# ThrusterBoardV1_1.net
KiCad netlist of a schematic drawn in EAGLE
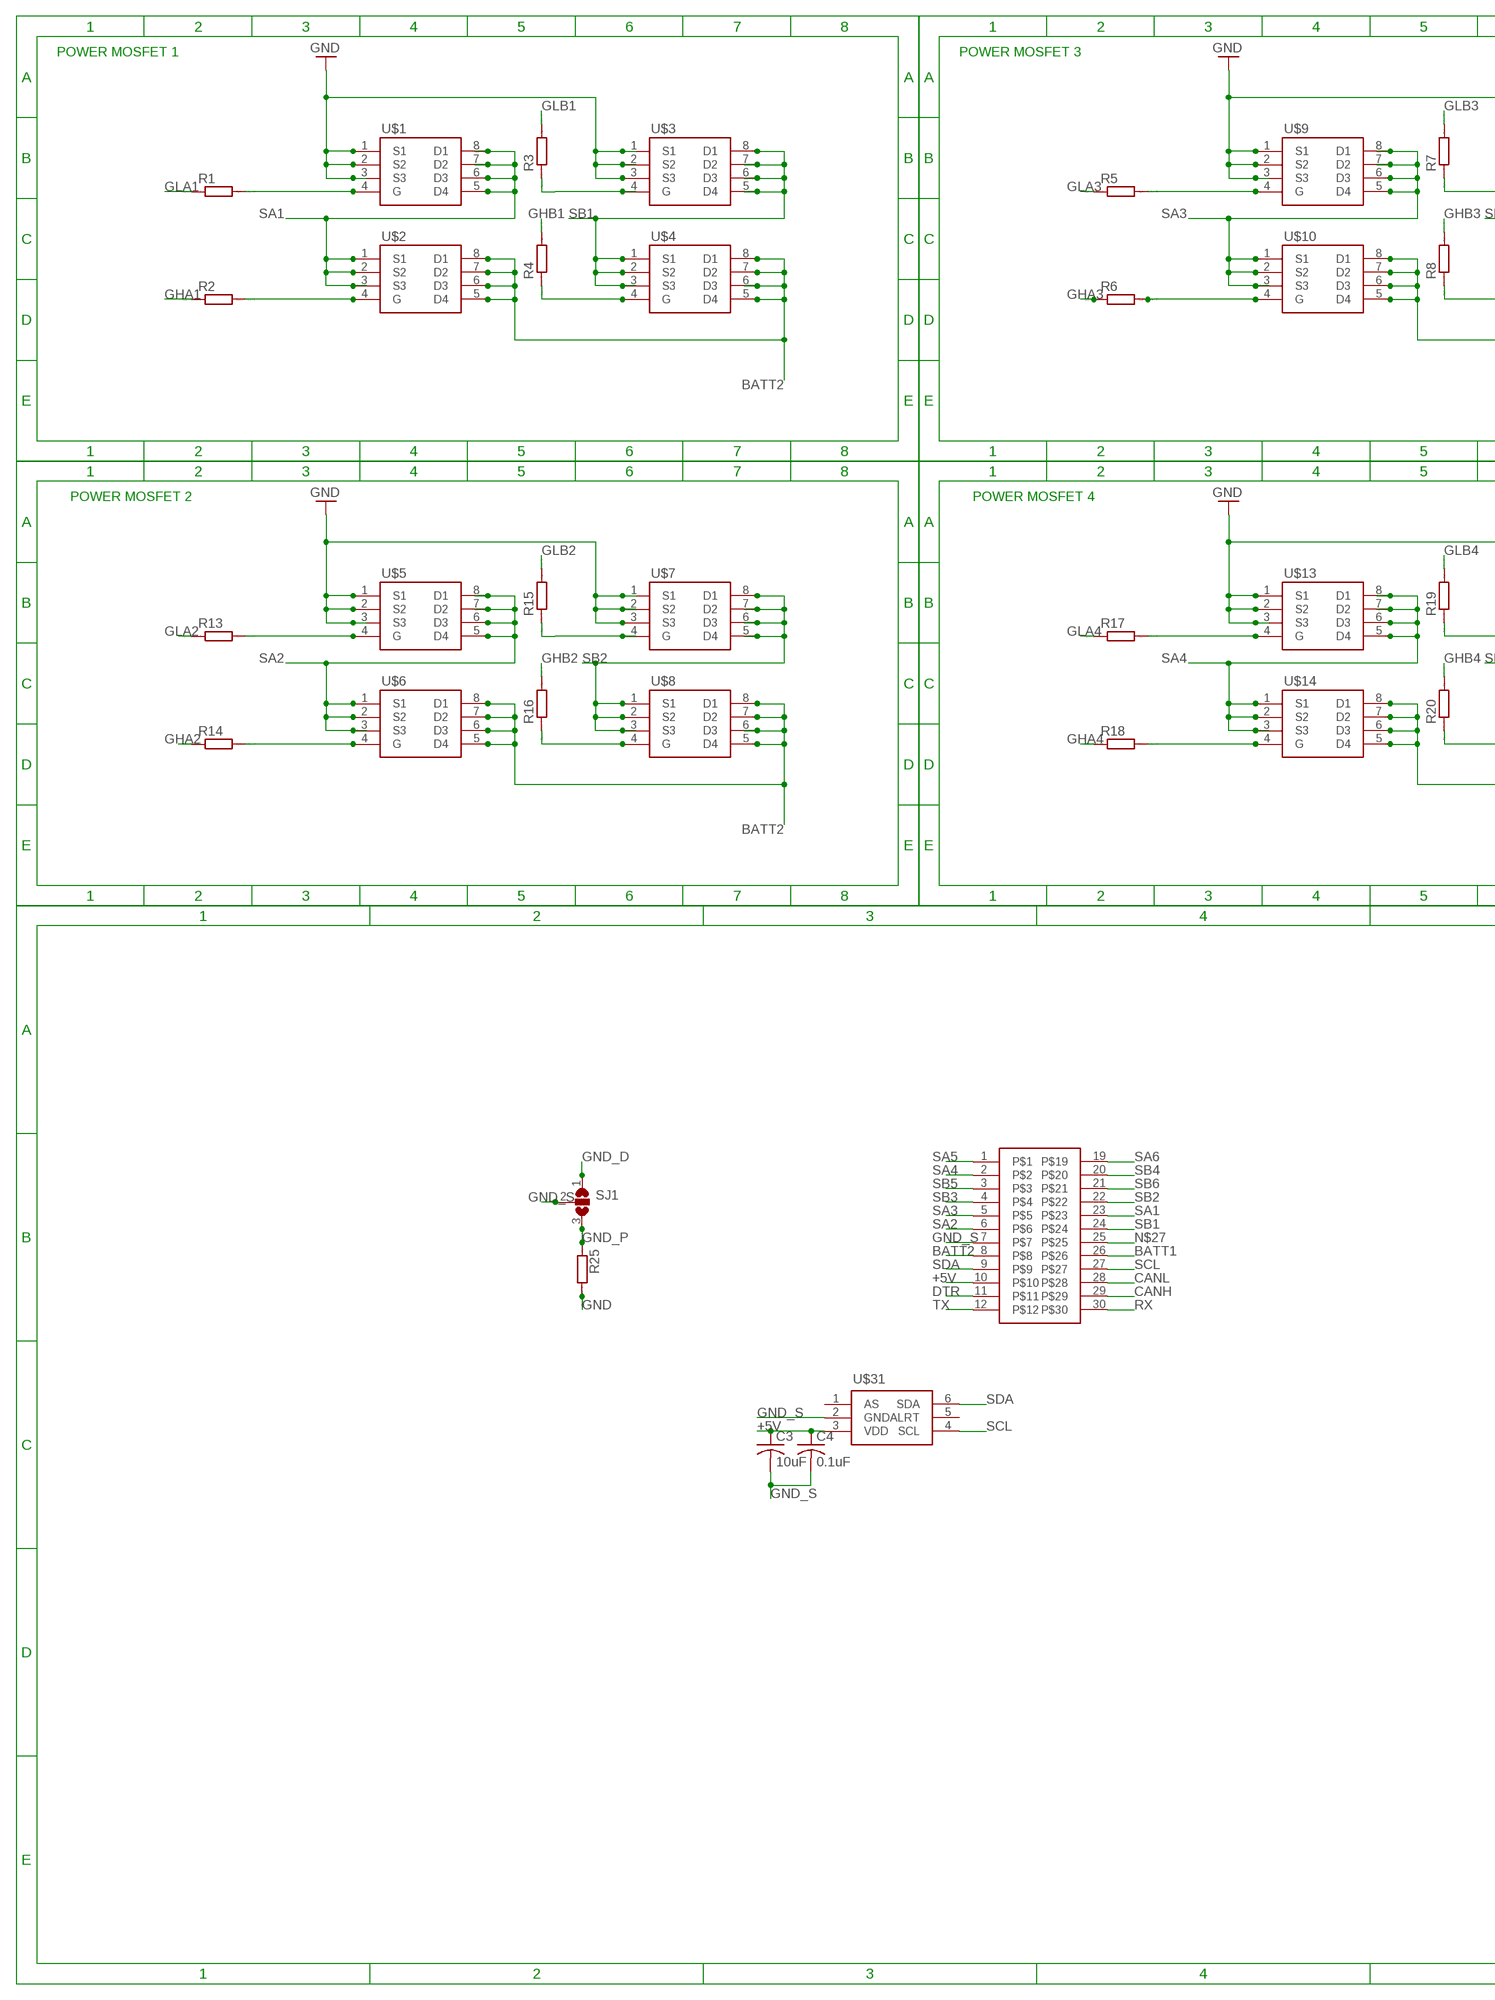
[diagram p0: schematic, sheet 1, part 1 of 2]
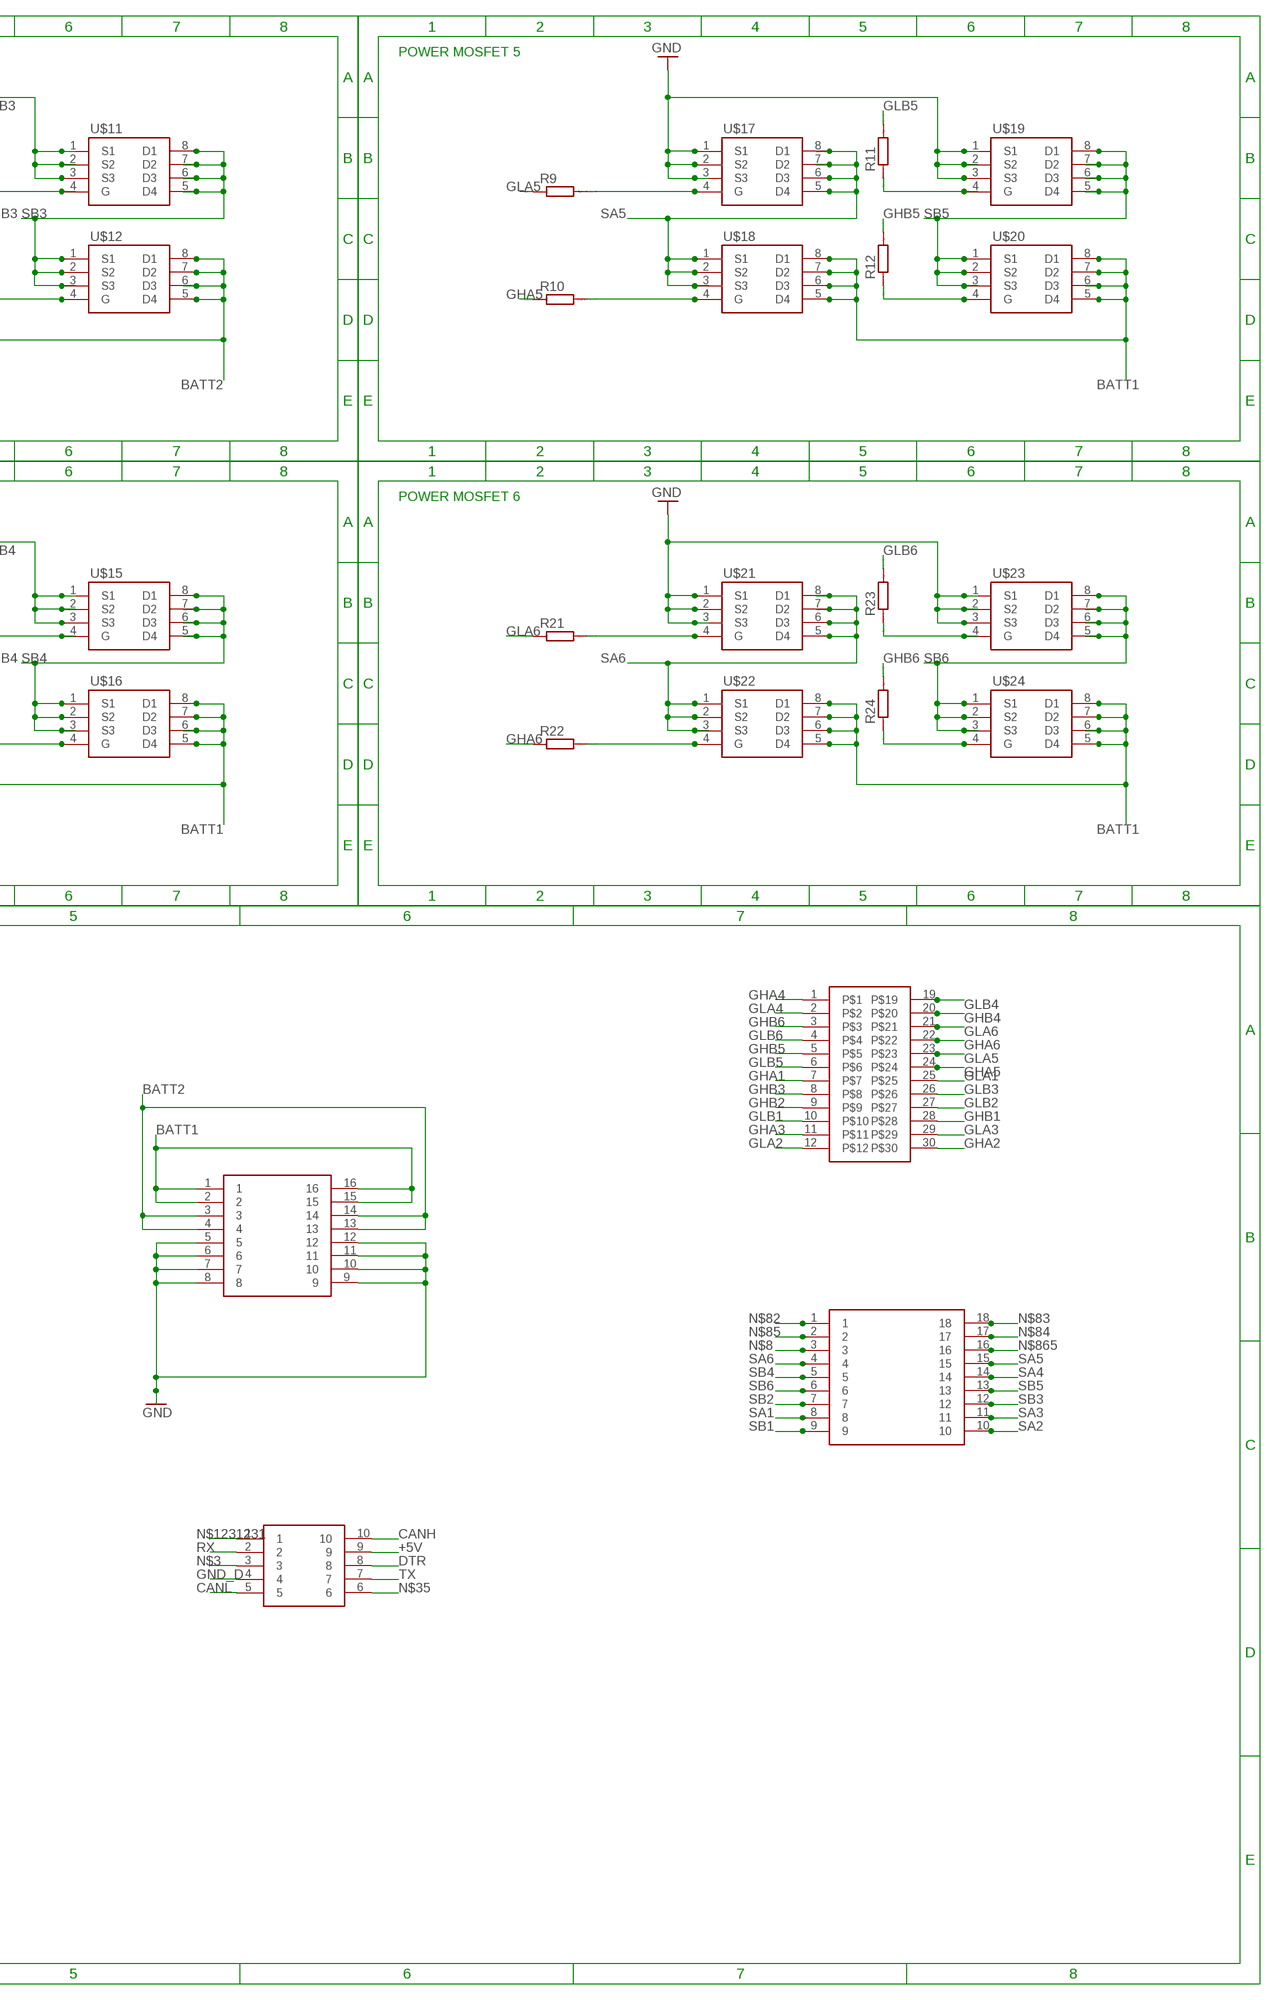
[diagram p1: schematic, sheet 1, part 2 of 2]

(export (version "E")
  (design (tool "Eeschema 10.0.6"))
  (components
    (comp (ref "C3")
      (value "10uF")
      (footprint "eagle-import:C0805")
      (libsource (lib "eagle-import") (part "C-USC0805"))
    )
    (comp (ref "C4")
      (value "0.1uF")
      (footprint "eagle-import:C0805")
      (libsource (lib "eagle-import") (part "C-USC0805"))
    )
    (comp (ref "R1") (value "R") (footprint "eagle-import:R0805") (libsource (lib "eagle-import") (part "R")))
    (comp (ref "R2") (value "R") (footprint "eagle-import:R0805") (libsource (lib "eagle-import") (part "R")))
    (comp (ref "R3") (value "R") (footprint "eagle-import:R0805") (libsource (lib "eagle-import") (part "R")))
    (comp (ref "R4") (value "R") (footprint "eagle-import:R0805") (libsource (lib "eagle-import") (part "R")))
    (comp (ref "R5") (value "R") (footprint "eagle-import:R0805") (libsource (lib "eagle-import") (part "R")))
    (comp (ref "R6") (value "R") (footprint "eagle-import:R0805") (libsource (lib "eagle-import") (part "R")))
    (comp (ref "R7") (value "R") (footprint "eagle-import:R0805") (libsource (lib "eagle-import") (part "R")))
    (comp (ref "R8") (value "R") (footprint "eagle-import:R0805") (libsource (lib "eagle-import") (part "R")))
    (comp (ref "R9") (value "R") (footprint "eagle-import:R0805") (libsource (lib "eagle-import") (part "R")))
    (comp (ref "R10")
      (value "R")
      (footprint "eagle-import:R0805")
      (libsource (lib "eagle-import") (part "R"))
    )
    (comp (ref "R11")
      (value "R")
      (footprint "eagle-import:R0805")
      (libsource (lib "eagle-import") (part "R"))
    )
    (comp (ref "R12")
      (value "R")
      (footprint "eagle-import:R0805")
      (libsource (lib "eagle-import") (part "R"))
    )
    (comp (ref "R13")
      (value "R")
      (footprint "eagle-import:R0805")
      (libsource (lib "eagle-import") (part "R"))
    )
    (comp (ref "R14")
      (value "R")
      (footprint "eagle-import:R0805")
      (libsource (lib "eagle-import") (part "R"))
    )
    (comp (ref "R15")
      (value "R")
      (footprint "eagle-import:R0805")
      (libsource (lib "eagle-import") (part "R"))
    )
    (comp (ref "R16")
      (value "R")
      (footprint "eagle-import:R0805")
      (libsource (lib "eagle-import") (part "R"))
    )
    (comp (ref "R17")
      (value "R")
      (footprint "eagle-import:R0805")
      (libsource (lib "eagle-import") (part "R"))
    )
    (comp (ref "R18")
      (value "R")
      (footprint "eagle-import:R0805")
      (libsource (lib "eagle-import") (part "R"))
    )
    (comp (ref "R19")
      (value "R")
      (footprint "eagle-import:R0805")
      (libsource (lib "eagle-import") (part "R"))
    )
    (comp (ref "R20")
      (value "R")
      (footprint "eagle-import:R0805")
      (libsource (lib "eagle-import") (part "R"))
    )
    (comp (ref "R21")
      (value "R")
      (footprint "eagle-import:R0805")
      (libsource (lib "eagle-import") (part "R"))
    )
    (comp (ref "R22")
      (value "R")
      (footprint "eagle-import:R0805")
      (libsource (lib "eagle-import") (part "R"))
    )
    (comp (ref "R23")
      (value "R")
      (footprint "eagle-import:R0805")
      (libsource (lib "eagle-import") (part "R"))
    )
    (comp (ref "R24")
      (value "R")
      (footprint "eagle-import:R0805")
      (libsource (lib "eagle-import") (part "R"))
    )
    (comp (ref "R25")
      (value "R")
      (footprint "eagle-import:R0805")
      (libsource (lib "eagle-import") (part "R"))
    )
    (comp (ref "SJ1")
      (value "SJ2W")
      (footprint "eagle-import:SJ_2")
      (libsource (lib "eagle-import") (part "SJ2W"))
    )
    (comp (ref "U$1")
      (value "IRF7842PBF")
      (footprint "eagle-import:SO-8")
      (libsource (lib "eagle-import") (part "IRF7842PBF"))
    )
    (comp (ref "U$2")
      (value "IRF7842PBF")
      (footprint "eagle-import:SO-8")
      (libsource (lib "eagle-import") (part "IRF7842PBF"))
    )
    (comp (ref "U$3")
      (value "IRF7842PBF")
      (footprint "eagle-import:SO-8")
      (libsource (lib "eagle-import") (part "IRF7842PBF"))
    )
    (comp (ref "U$4")
      (value "IRF7842PBF")
      (footprint "eagle-import:SO-8")
      (libsource (lib "eagle-import") (part "IRF7842PBF"))
    )
    (comp (ref "U$5")
      (value "IRF7842PBF")
      (footprint "eagle-import:SO-8")
      (libsource (lib "eagle-import") (part "IRF7842PBF"))
    )
    (comp (ref "U$6")
      (value "IRF7842PBF")
      (footprint "eagle-import:SO-8")
      (libsource (lib "eagle-import") (part "IRF7842PBF"))
    )
    (comp (ref "U$7")
      (value "IRF7842PBF")
      (footprint "eagle-import:SO-8")
      (libsource (lib "eagle-import") (part "IRF7842PBF"))
    )
    (comp (ref "U$8")
      (value "IRF7842PBF")
      (footprint "eagle-import:SO-8")
      (libsource (lib "eagle-import") (part "IRF7842PBF"))
    )
    (comp (ref "U$9")
      (value "IRF7842PBF")
      (footprint "eagle-import:SO-8")
      (libsource (lib "eagle-import") (part "IRF7842PBF"))
    )
    (comp (ref "U$10")
      (value "IRF7842PBF")
      (footprint "eagle-import:SO-8")
      (libsource (lib "eagle-import") (part "IRF7842PBF"))
    )
    (comp (ref "U$11")
      (value "IRF7842PBF")
      (footprint "eagle-import:SO-8")
      (libsource (lib "eagle-import") (part "IRF7842PBF"))
    )
    (comp (ref "U$12")
      (value "IRF7842PBF")
      (footprint "eagle-import:SO-8")
      (libsource (lib "eagle-import") (part "IRF7842PBF"))
    )
    (comp (ref "U$13")
      (value "IRF7842PBF")
      (footprint "eagle-import:SO-8")
      (libsource (lib "eagle-import") (part "IRF7842PBF"))
    )
    (comp (ref "U$14")
      (value "IRF7842PBF")
      (footprint "eagle-import:SO-8")
      (libsource (lib "eagle-import") (part "IRF7842PBF"))
    )
    (comp (ref "U$15")
      (value "IRF7842PBF")
      (footprint "eagle-import:SO-8")
      (libsource (lib "eagle-import") (part "IRF7842PBF"))
    )
    (comp (ref "U$16")
      (value "IRF7842PBF")
      (footprint "eagle-import:SO-8")
      (libsource (lib "eagle-import") (part "IRF7842PBF"))
    )
    (comp (ref "U$17")
      (value "IRF7842PBF")
      (footprint "eagle-import:SO-8")
      (libsource (lib "eagle-import") (part "IRF7842PBF"))
    )
    (comp (ref "U$18")
      (value "IRF7842PBF")
      (footprint "eagle-import:SO-8")
      (libsource (lib "eagle-import") (part "IRF7842PBF"))
    )
    (comp (ref "U$19")
      (value "IRF7842PBF")
      (footprint "eagle-import:SO-8")
      (libsource (lib "eagle-import") (part "IRF7842PBF"))
    )
    (comp (ref "U$20")
      (value "IRF7842PBF")
      (footprint "eagle-import:SO-8")
      (libsource (lib "eagle-import") (part "IRF7842PBF"))
    )
    (comp (ref "U$21")
      (value "IRF7842PBF")
      (footprint "eagle-import:SO-8")
      (libsource (lib "eagle-import") (part "IRF7842PBF"))
    )
    (comp (ref "U$22")
      (value "IRF7842PBF")
      (footprint "eagle-import:SO-8")
      (libsource (lib "eagle-import") (part "IRF7842PBF"))
    )
    (comp (ref "U$23")
      (value "IRF7842PBF")
      (footprint "eagle-import:SO-8")
      (libsource (lib "eagle-import") (part "IRF7842PBF"))
    )
    (comp (ref "U$24")
      (value "IRF7842PBF")
      (footprint "eagle-import:SO-8")
      (libsource (lib "eagle-import") (part "IRF7842PBF"))
    )
    (comp (ref "U$25")
      (value "15-24-6163")
      (footprint "eagle-import:15-24-6163")
      (libsource (lib "eagle-import") (part "15-24-6163"))
    )
    (comp (ref "U$26")
      (value "50-36-1836")
      (footprint "eagle-import:50-36-1836")
      (libsource (lib "eagle-import") (part "50-36-1836"))
    )
    (comp (ref "U$27")
      (value "15-24-6103")
      (footprint "eagle-import:15-24-6103")
      (libsource (lib "eagle-import") (part "15-24-6103"))
    )
    (comp (ref "U$28")
      (value "15-45-3136")
      (footprint "eagle-import:15-45-3136")
      (libsource (lib "eagle-import") (part "15-45-3136"))
    )
    (comp (ref "U$29")
      (value "15-45-3136")
      (footprint "eagle-import:15-45-3136")
      (libsource (lib "eagle-import") (part "15-45-3136"))
    )
    (comp (ref "U$31")
      (value "AD7414")
      (footprint "eagle-import:SOT23-6")
      (libsource (lib "eagle-import") (part "AD7414"))
    )
  )
  (nets
    (net (code "1") (name "/+5V") (class "Default")
      (node (ref "C3") (pin "1") (pinfunction "1_1") (pintype "passive"))
      (node (ref "C4") (pin "1") (pinfunction "1_1") (pintype "passive"))
      (node (ref "U$27") (pin "9") (pinfunction "9_9") (pintype "bidirectional"))
      (node (ref "U$29") (pin "10") (pinfunction "P$10_10") (pintype "bidirectional"))
      (node (ref "U$31") (pin "3") (pinfunction "VDD_3") (pintype "bidirectional"))
    )
    (net (code "2") (name "/BATT1") (class "Default")
      (node (ref "U$14") (pin "5") (pinfunction "D4_5") (pintype "bidirectional"))
      (node (ref "U$14") (pin "6") (pinfunction "D3_6") (pintype "bidirectional"))
      (node (ref "U$14") (pin "7") (pinfunction "D2_7") (pintype "bidirectional"))
      (node (ref "U$14") (pin "8") (pinfunction "D1_8") (pintype "bidirectional"))
      (node (ref "U$16") (pin "5") (pinfunction "D4_5") (pintype "bidirectional"))
      (node (ref "U$16") (pin "6") (pinfunction "D3_6") (pintype "bidirectional"))
      (node (ref "U$16") (pin "7") (pinfunction "D2_7") (pintype "bidirectional"))
      (node (ref "U$16") (pin "8") (pinfunction "D1_8") (pintype "bidirectional"))
      (node (ref "U$18") (pin "5") (pinfunction "D4_5") (pintype "bidirectional"))
      (node (ref "U$18") (pin "6") (pinfunction "D3_6") (pintype "bidirectional"))
      (node (ref "U$18") (pin "7") (pinfunction "D2_7") (pintype "bidirectional"))
      (node (ref "U$18") (pin "8") (pinfunction "D1_8") (pintype "bidirectional"))
      (node (ref "U$20") (pin "5") (pinfunction "D4_5") (pintype "bidirectional"))
      (node (ref "U$20") (pin "6") (pinfunction "D3_6") (pintype "bidirectional"))
      (node (ref "U$20") (pin "7") (pinfunction "D2_7") (pintype "bidirectional"))
      (node (ref "U$20") (pin "8") (pinfunction "D1_8") (pintype "bidirectional"))
      (node (ref "U$22") (pin "5") (pinfunction "D4_5") (pintype "bidirectional"))
      (node (ref "U$22") (pin "6") (pinfunction "D3_6") (pintype "bidirectional"))
      (node (ref "U$22") (pin "7") (pinfunction "D2_7") (pintype "bidirectional"))
      (node (ref "U$22") (pin "8") (pinfunction "D1_8") (pintype "bidirectional"))
      (node (ref "U$24") (pin "5") (pinfunction "D4_5") (pintype "bidirectional"))
      (node (ref "U$24") (pin "6") (pinfunction "D3_6") (pintype "bidirectional"))
      (node (ref "U$24") (pin "7") (pinfunction "D2_7") (pintype "bidirectional"))
      (node (ref "U$24") (pin "8") (pinfunction "D1_8") (pintype "bidirectional"))
      (node (ref "U$25") (pin "1") (pinfunction "1_1") (pintype "bidirectional"))
      (node (ref "U$25") (pin "15") (pinfunction "15_15") (pintype "bidirectional"))
      (node (ref "U$25") (pin "16") (pinfunction "16_16") (pintype "bidirectional"))
      (node (ref "U$25") (pin "2") (pinfunction "2_2") (pintype "bidirectional"))
      (node (ref "U$29") (pin "26") (pinfunction "P$26_26") (pintype "bidirectional"))
    )
    (net (code "3") (name "/BATT2") (class "Default")
      (node (ref "U$10") (pin "5") (pinfunction "D4_5") (pintype "bidirectional"))
      (node (ref "U$10") (pin "6") (pinfunction "D3_6") (pintype "bidirectional"))
      (node (ref "U$10") (pin "7") (pinfunction "D2_7") (pintype "bidirectional"))
      (node (ref "U$10") (pin "8") (pinfunction "D1_8") (pintype "bidirectional"))
      (node (ref "U$12") (pin "5") (pinfunction "D4_5") (pintype "bidirectional"))
      (node (ref "U$12") (pin "6") (pinfunction "D3_6") (pintype "bidirectional"))
      (node (ref "U$12") (pin "7") (pinfunction "D2_7") (pintype "bidirectional"))
      (node (ref "U$12") (pin "8") (pinfunction "D1_8") (pintype "bidirectional"))
      (node (ref "U$2") (pin "5") (pinfunction "D4_5") (pintype "bidirectional"))
      (node (ref "U$2") (pin "6") (pinfunction "D3_6") (pintype "bidirectional"))
      (node (ref "U$2") (pin "7") (pinfunction "D2_7") (pintype "bidirectional"))
      (node (ref "U$2") (pin "8") (pinfunction "D1_8") (pintype "bidirectional"))
      (node (ref "U$25") (pin "13") (pinfunction "13_13") (pintype "bidirectional"))
      (node (ref "U$25") (pin "14") (pinfunction "14_14") (pintype "bidirectional"))
      (node (ref "U$25") (pin "3") (pinfunction "3_3") (pintype "bidirectional"))
      (node (ref "U$25") (pin "4") (pinfunction "4_4") (pintype "bidirectional"))
      (node (ref "U$29") (pin "8") (pinfunction "P$8_8") (pintype "bidirectional"))
      (node (ref "U$4") (pin "5") (pinfunction "D4_5") (pintype "bidirectional"))
      (node (ref "U$4") (pin "6") (pinfunction "D3_6") (pintype "bidirectional"))
      (node (ref "U$4") (pin "7") (pinfunction "D2_7") (pintype "bidirectional"))
      (node (ref "U$4") (pin "8") (pinfunction "D1_8") (pintype "bidirectional"))
      (node (ref "U$6") (pin "5") (pinfunction "D4_5") (pintype "bidirectional"))
      (node (ref "U$6") (pin "6") (pinfunction "D3_6") (pintype "bidirectional"))
      (node (ref "U$6") (pin "7") (pinfunction "D2_7") (pintype "bidirectional"))
      (node (ref "U$6") (pin "8") (pinfunction "D1_8") (pintype "bidirectional"))
      (node (ref "U$8") (pin "5") (pinfunction "D4_5") (pintype "bidirectional"))
      (node (ref "U$8") (pin "6") (pinfunction "D3_6") (pintype "bidirectional"))
      (node (ref "U$8") (pin "7") (pinfunction "D2_7") (pintype "bidirectional"))
      (node (ref "U$8") (pin "8") (pinfunction "D1_8") (pintype "bidirectional"))
    )
    (net (code "4") (name "/CANH") (class "Default")
      (node (ref "U$27") (pin "10") (pinfunction "10_10") (pintype "bidirectional"))
      (node (ref "U$29") (pin "29") (pinfunction "P$29_29") (pintype "bidirectional"))
    )
    (net (code "5") (name "/CANL") (class "Default")
      (node (ref "U$27") (pin "5") (pinfunction "5_5") (pintype "bidirectional"))
      (node (ref "U$29") (pin "28") (pinfunction "P$28_28") (pintype "bidirectional"))
    )
    (net (code "6") (name "/DTR") (class "Default")
      (node (ref "U$27") (pin "8") (pinfunction "8_8") (pintype "bidirectional"))
      (node (ref "U$29") (pin "11") (pinfunction "P$11_11") (pintype "bidirectional"))
    )
    (net (code "7") (name "/GHA1") (class "Default")
      (node (ref "R2") (pin "1") (pinfunction "1_1") (pintype "passive"))
      (node (ref "U$28") (pin "7") (pinfunction "P$7_7") (pintype "bidirectional"))
    )
    (net (code "8") (name "/GHA2") (class "Default")
      (node (ref "R14") (pin "1") (pinfunction "1_1") (pintype "passive"))
      (node (ref "U$28") (pin "30") (pinfunction "P$30_30") (pintype "bidirectional"))
    )
    (net (code "9") (name "/GHA3") (class "Default")
      (node (ref "R6") (pin "1") (pinfunction "1_1") (pintype "passive"))
      (node (ref "U$28") (pin "11") (pinfunction "P$11_11") (pintype "bidirectional"))
    )
    (net (code "10") (name "/GHA4") (class "Default")
      (node (ref "R18") (pin "1") (pinfunction "1_1") (pintype "passive"))
      (node (ref "U$28") (pin "1") (pinfunction "P$1_1") (pintype "bidirectional"))
    )
    (net (code "11") (name "/GHA5") (class "Default")
      (node (ref "R10") (pin "1") (pinfunction "1_1") (pintype "passive"))
      (node (ref "U$28") (pin "24") (pinfunction "P$24_24") (pintype "bidirectional"))
    )
    (net (code "12") (name "/GHA6") (class "Default")
      (node (ref "R22") (pin "1") (pinfunction "1_1") (pintype "passive"))
      (node (ref "U$28") (pin "22") (pinfunction "P$22_22") (pintype "bidirectional"))
    )
    (net (code "13") (name "/GHB1") (class "Default")
      (node (ref "R4") (pin "2") (pinfunction "2_2") (pintype "passive"))
      (node (ref "U$28") (pin "28") (pinfunction "P$28_28") (pintype "bidirectional"))
    )
    (net (code "14") (name "/GHB2") (class "Default")
      (node (ref "R16") (pin "2") (pinfunction "2_2") (pintype "passive"))
      (node (ref "U$28") (pin "9") (pinfunction "P$9_9") (pintype "bidirectional"))
    )
    (net (code "15") (name "/GHB3") (class "Default")
      (node (ref "R8") (pin "2") (pinfunction "2_2") (pintype "passive"))
      (node (ref "U$28") (pin "8") (pinfunction "P$8_8") (pintype "bidirectional"))
    )
    (net (code "16") (name "/GHB4") (class "Default")
      (node (ref "R20") (pin "2") (pinfunction "2_2") (pintype "passive"))
      (node (ref "U$28") (pin "20") (pinfunction "P$20_20") (pintype "bidirectional"))
    )
    (net (code "17") (name "/GHB5") (class "Default")
      (node (ref "R12") (pin "2") (pinfunction "2_2") (pintype "passive"))
      (node (ref "U$28") (pin "5") (pinfunction "P$5_5") (pintype "bidirectional"))
    )
    (net (code "18") (name "/GHB6") (class "Default")
      (node (ref "R24") (pin "2") (pinfunction "2_2") (pintype "passive"))
      (node (ref "U$28") (pin "3") (pinfunction "P$3_3") (pintype "bidirectional"))
    )
    (net (code "19") (name "/GLA1") (class "Default")
      (node (ref "R1") (pin "1") (pinfunction "1_1") (pintype "passive"))
      (node (ref "U$28") (pin "25") (pinfunction "P$25_25") (pintype "bidirectional"))
    )
    (net (code "20") (name "/GLA2") (class "Default")
      (node (ref "R13") (pin "1") (pinfunction "1_1") (pintype "passive"))
      (node (ref "U$28") (pin "12") (pinfunction "P$12_12") (pintype "bidirectional"))
    )
    (net (code "21") (name "/GLA3") (class "Default")
      (node (ref "R5") (pin "1") (pinfunction "1_1") (pintype "passive"))
      (node (ref "U$28") (pin "29") (pinfunction "P$29_29") (pintype "bidirectional"))
    )
    (net (code "22") (name "/GLA4") (class "Default")
      (node (ref "R17") (pin "1") (pinfunction "1_1") (pintype "passive"))
      (node (ref "U$28") (pin "2") (pinfunction "P$2_2") (pintype "bidirectional"))
    )
    (net (code "23") (name "/GLA5") (class "Default")
      (node (ref "R9") (pin "1") (pinfunction "1_1") (pintype "passive"))
      (node (ref "U$28") (pin "23") (pinfunction "P$23_23") (pintype "bidirectional"))
    )
    (net (code "24") (name "/GLA6") (class "Default")
      (node (ref "R21") (pin "1") (pinfunction "1_1") (pintype "passive"))
      (node (ref "U$28") (pin "21") (pinfunction "P$21_21") (pintype "bidirectional"))
    )
    (net (code "25") (name "/GLB1") (class "Default")
      (node (ref "R3") (pin "2") (pinfunction "2_2") (pintype "passive"))
      (node (ref "U$28") (pin "10") (pinfunction "P$10_10") (pintype "bidirectional"))
    )
    (net (code "26") (name "/GLB2") (class "Default")
      (node (ref "R15") (pin "2") (pinfunction "2_2") (pintype "passive"))
      (node (ref "U$28") (pin "27") (pinfunction "P$27_27") (pintype "bidirectional"))
    )
    (net (code "27") (name "/GLB3") (class "Default")
      (node (ref "R7") (pin "2") (pinfunction "2_2") (pintype "passive"))
      (node (ref "U$28") (pin "26") (pinfunction "P$26_26") (pintype "bidirectional"))
    )
    (net (code "28") (name "/GLB4") (class "Default")
      (node (ref "R19") (pin "2") (pinfunction "2_2") (pintype "passive"))
      (node (ref "U$28") (pin "19") (pinfunction "P$19_19") (pintype "bidirectional"))
    )
    (net (code "29") (name "/GLB5") (class "Default")
      (node (ref "R11") (pin "2") (pinfunction "2_2") (pintype "passive"))
      (node (ref "U$28") (pin "6") (pinfunction "P$6_6") (pintype "bidirectional"))
    )
    (net (code "30") (name "/GLB6") (class "Default")
      (node (ref "R23") (pin "2") (pinfunction "2_2") (pintype "passive"))
      (node (ref "U$28") (pin "4") (pinfunction "P$4_4") (pintype "bidirectional"))
    )
    (net (code "31") (name "/GND_D") (class "Default")
      (node (ref "SJ1") (pin "1") (pinfunction "1_1") (pintype "passive"))
      (node (ref "U$27") (pin "4") (pinfunction "4_4") (pintype "bidirectional"))
    )
    (net (code "32") (name "/GND_P") (class "Default")
      (node (ref "R25") (pin "1") (pinfunction "1_1") (pintype "passive"))
      (node (ref "SJ1") (pin "3") (pinfunction "3_3") (pintype "passive"))
    )
    (net (code "33") (name "/GND_S") (class "Default")
      (node (ref "C3") (pin "2") (pinfunction "2_2") (pintype "passive"))
      (node (ref "C4") (pin "2") (pinfunction "2_2") (pintype "passive"))
      (node (ref "SJ1") (pin "2") (pinfunction "2_2") (pintype "passive"))
      (node (ref "U$29") (pin "7") (pinfunction "P$7_7") (pintype "bidirectional"))
      (node (ref "U$31") (pin "2") (pinfunction "GND_2") (pintype "bidirectional"))
    )
    (net (code "34") (name "/N$3") (class "Default")
      (node (ref "U$27") (pin "3") (pinfunction "3_3") (pintype "bidirectional"))
    )
    (net (code "35") (name "/N$8") (class "Default")
      (node (ref "U$26") (pin "3") (pinfunction "3_3") (pintype "bidirectional"))
    )
    (net (code "36") (name "/N$27") (class "Default")
      (node (ref "U$29") (pin "25") (pinfunction "P$25_25") (pintype "bidirectional"))
    )
    (net (code "37") (name "/N$35") (class "Default")
      (node (ref "U$27") (pin "6") (pinfunction "6_6") (pintype "bidirectional"))
    )
    (net (code "38") (name "/N$82") (class "Default")
      (node (ref "U$26") (pin "1") (pinfunction "1_1") (pintype "bidirectional"))
    )
    (net (code "39") (name "/N$83") (class "Default")
      (node (ref "U$26") (pin "18") (pinfunction "18_18") (pintype "bidirectional"))
    )
    (net (code "40") (name "/N$84") (class "Default")
      (node (ref "U$26") (pin "17") (pinfunction "17_17") (pintype "bidirectional"))
    )
    (net (code "41") (name "/N$85") (class "Default")
      (node (ref "U$26") (pin "2") (pinfunction "2_2") (pintype "bidirectional"))
    )
    (net (code "42") (name "/N$865") (class "Default")
      (node (ref "U$26") (pin "16") (pinfunction "16_16") (pintype "bidirectional"))
    )
    (net (code "43") (name "/N$1231231") (class "Default")
      (node (ref "U$27") (pin "1") (pinfunction "1_1") (pintype "bidirectional"))
    )
    (net (code "44") (name "/RX") (class "Default")
      (node (ref "U$27") (pin "2") (pinfunction "2_2") (pintype "bidirectional"))
      (node (ref "U$29") (pin "30") (pinfunction "P$30_30") (pintype "bidirectional"))
    )
    (net (code "45") (name "/SA1") (class "Default")
      (node (ref "U$1") (pin "5") (pinfunction "D4_5") (pintype "bidirectional"))
      (node (ref "U$1") (pin "6") (pinfunction "D3_6") (pintype "bidirectional"))
      (node (ref "U$1") (pin "7") (pinfunction "D2_7") (pintype "bidirectional"))
      (node (ref "U$1") (pin "8") (pinfunction "D1_8") (pintype "bidirectional"))
      (node (ref "U$2") (pin "1") (pinfunction "S1_1") (pintype "bidirectional"))
      (node (ref "U$2") (pin "2") (pinfunction "S2_2") (pintype "bidirectional"))
      (node (ref "U$2") (pin "3") (pinfunction "S3_3") (pintype "bidirectional"))
      (node (ref "U$26") (pin "8") (pinfunction "8_8") (pintype "bidirectional"))
      (node (ref "U$29") (pin "23") (pinfunction "P$23_23") (pintype "bidirectional"))
    )
    (net (code "46") (name "/SA2") (class "Default")
      (node (ref "U$26") (pin "10") (pinfunction "10_10") (pintype "bidirectional"))
      (node (ref "U$29") (pin "6") (pinfunction "P$6_6") (pintype "bidirectional"))
      (node (ref "U$5") (pin "5") (pinfunction "D4_5") (pintype "bidirectional"))
      (node (ref "U$5") (pin "6") (pinfunction "D3_6") (pintype "bidirectional"))
      (node (ref "U$5") (pin "7") (pinfunction "D2_7") (pintype "bidirectional"))
      (node (ref "U$5") (pin "8") (pinfunction "D1_8") (pintype "bidirectional"))
      (node (ref "U$6") (pin "1") (pinfunction "S1_1") (pintype "bidirectional"))
      (node (ref "U$6") (pin "2") (pinfunction "S2_2") (pintype "bidirectional"))
      (node (ref "U$6") (pin "3") (pinfunction "S3_3") (pintype "bidirectional"))
    )
    (net (code "47") (name "/SA3") (class "Default")
      (node (ref "U$10") (pin "1") (pinfunction "S1_1") (pintype "bidirectional"))
      (node (ref "U$10") (pin "2") (pinfunction "S2_2") (pintype "bidirectional"))
      (node (ref "U$10") (pin "3") (pinfunction "S3_3") (pintype "bidirectional"))
      (node (ref "U$26") (pin "11") (pinfunction "11_11") (pintype "bidirectional"))
      (node (ref "U$29") (pin "5") (pinfunction "P$5_5") (pintype "bidirectional"))
      (node (ref "U$9") (pin "5") (pinfunction "D4_5") (pintype "bidirectional"))
      (node (ref "U$9") (pin "6") (pinfunction "D3_6") (pintype "bidirectional"))
      (node (ref "U$9") (pin "7") (pinfunction "D2_7") (pintype "bidirectional"))
      (node (ref "U$9") (pin "8") (pinfunction "D1_8") (pintype "bidirectional"))
    )
    (net (code "48") (name "/SA4") (class "Default")
      (node (ref "U$13") (pin "5") (pinfunction "D4_5") (pintype "bidirectional"))
      (node (ref "U$13") (pin "6") (pinfunction "D3_6") (pintype "bidirectional"))
      (node (ref "U$13") (pin "7") (pinfunction "D2_7") (pintype "bidirectional"))
      (node (ref "U$13") (pin "8") (pinfunction "D1_8") (pintype "bidirectional"))
      (node (ref "U$14") (pin "1") (pinfunction "S1_1") (pintype "bidirectional"))
      (node (ref "U$14") (pin "2") (pinfunction "S2_2") (pintype "bidirectional"))
      (node (ref "U$14") (pin "3") (pinfunction "S3_3") (pintype "bidirectional"))
      (node (ref "U$26") (pin "14") (pinfunction "14_14") (pintype "bidirectional"))
      (node (ref "U$29") (pin "2") (pinfunction "P$2_2") (pintype "bidirectional"))
    )
    (net (code "49") (name "/SA5") (class "Default")
      (node (ref "U$17") (pin "5") (pinfunction "D4_5") (pintype "bidirectional"))
      (node (ref "U$17") (pin "6") (pinfunction "D3_6") (pintype "bidirectional"))
      (node (ref "U$17") (pin "7") (pinfunction "D2_7") (pintype "bidirectional"))
      (node (ref "U$17") (pin "8") (pinfunction "D1_8") (pintype "bidirectional"))
      (node (ref "U$18") (pin "1") (pinfunction "S1_1") (pintype "bidirectional"))
      (node (ref "U$18") (pin "2") (pinfunction "S2_2") (pintype "bidirectional"))
      (node (ref "U$18") (pin "3") (pinfunction "S3_3") (pintype "bidirectional"))
      (node (ref "U$26") (pin "15") (pinfunction "15_15") (pintype "bidirectional"))
      (node (ref "U$29") (pin "1") (pinfunction "P$1_1") (pintype "bidirectional"))
    )
    (net (code "50") (name "/SA6") (class "Default")
      (node (ref "U$21") (pin "5") (pinfunction "D4_5") (pintype "bidirectional"))
      (node (ref "U$21") (pin "6") (pinfunction "D3_6") (pintype "bidirectional"))
      (node (ref "U$21") (pin "7") (pinfunction "D2_7") (pintype "bidirectional"))
      (node (ref "U$21") (pin "8") (pinfunction "D1_8") (pintype "bidirectional"))
      (node (ref "U$22") (pin "1") (pinfunction "S1_1") (pintype "bidirectional"))
      (node (ref "U$22") (pin "2") (pinfunction "S2_2") (pintype "bidirectional"))
      (node (ref "U$22") (pin "3") (pinfunction "S3_3") (pintype "bidirectional"))
      (node (ref "U$26") (pin "4") (pinfunction "4_4") (pintype "bidirectional"))
      (node (ref "U$29") (pin "19") (pinfunction "P$19_19") (pintype "bidirectional"))
    )
    (net (code "51") (name "/SB1") (class "Default")
      (node (ref "U$26") (pin "9") (pinfunction "9_9") (pintype "bidirectional"))
      (node (ref "U$29") (pin "24") (pinfunction "P$24_24") (pintype "bidirectional"))
      (node (ref "U$3") (pin "5") (pinfunction "D4_5") (pintype "bidirectional"))
      (node (ref "U$3") (pin "6") (pinfunction "D3_6") (pintype "bidirectional"))
      (node (ref "U$3") (pin "7") (pinfunction "D2_7") (pintype "bidirectional"))
      (node (ref "U$3") (pin "8") (pinfunction "D1_8") (pintype "bidirectional"))
      (node (ref "U$4") (pin "1") (pinfunction "S1_1") (pintype "bidirectional"))
      (node (ref "U$4") (pin "2") (pinfunction "S2_2") (pintype "bidirectional"))
      (node (ref "U$4") (pin "3") (pinfunction "S3_3") (pintype "bidirectional"))
    )
    (net (code "52") (name "/SB2") (class "Default")
      (node (ref "U$26") (pin "7") (pinfunction "7_7") (pintype "bidirectional"))
      (node (ref "U$29") (pin "22") (pinfunction "P$22_22") (pintype "bidirectional"))
      (node (ref "U$7") (pin "5") (pinfunction "D4_5") (pintype "bidirectional"))
      (node (ref "U$7") (pin "6") (pinfunction "D3_6") (pintype "bidirectional"))
      (node (ref "U$7") (pin "7") (pinfunction "D2_7") (pintype "bidirectional"))
      (node (ref "U$7") (pin "8") (pinfunction "D1_8") (pintype "bidirectional"))
      (node (ref "U$8") (pin "1") (pinfunction "S1_1") (pintype "bidirectional"))
      (node (ref "U$8") (pin "2") (pinfunction "S2_2") (pintype "bidirectional"))
      (node (ref "U$8") (pin "3") (pinfunction "S3_3") (pintype "bidirectional"))
    )
    (net (code "53") (name "/SB3") (class "Default")
      (node (ref "U$11") (pin "5") (pinfunction "D4_5") (pintype "bidirectional"))
      (node (ref "U$11") (pin "6") (pinfunction "D3_6") (pintype "bidirectional"))
      (node (ref "U$11") (pin "7") (pinfunction "D2_7") (pintype "bidirectional"))
      (node (ref "U$11") (pin "8") (pinfunction "D1_8") (pintype "bidirectional"))
      (node (ref "U$12") (pin "1") (pinfunction "S1_1") (pintype "bidirectional"))
      (node (ref "U$12") (pin "2") (pinfunction "S2_2") (pintype "bidirectional"))
      (node (ref "U$12") (pin "3") (pinfunction "S3_3") (pintype "bidirectional"))
      (node (ref "U$26") (pin "12") (pinfunction "12_12") (pintype "bidirectional"))
      (node (ref "U$29") (pin "4") (pinfunction "P$4_4") (pintype "bidirectional"))
    )
    (net (code "54") (name "/SB4") (class "Default")
      (node (ref "U$15") (pin "5") (pinfunction "D4_5") (pintype "bidirectional"))
      (node (ref "U$15") (pin "6") (pinfunction "D3_6") (pintype "bidirectional"))
      (node (ref "U$15") (pin "7") (pinfunction "D2_7") (pintype "bidirectional"))
      (node (ref "U$15") (pin "8") (pinfunction "D1_8") (pintype "bidirectional"))
      (node (ref "U$16") (pin "1") (pinfunction "S1_1") (pintype "bidirectional"))
      (node (ref "U$16") (pin "2") (pinfunction "S2_2") (pintype "bidirectional"))
      (node (ref "U$16") (pin "3") (pinfunction "S3_3") (pintype "bidirectional"))
      (node (ref "U$26") (pin "5") (pinfunction "5_5") (pintype "bidirectional"))
      (node (ref "U$29") (pin "20") (pinfunction "P$20_20") (pintype "bidirectional"))
    )
    (net (code "55") (name "/SB5") (class "Default")
      (node (ref "U$19") (pin "5") (pinfunction "D4_5") (pintype "bidirectional"))
      (node (ref "U$19") (pin "6") (pinfunction "D3_6") (pintype "bidirectional"))
      (node (ref "U$19") (pin "7") (pinfunction "D2_7") (pintype "bidirectional"))
      (node (ref "U$19") (pin "8") (pinfunction "D1_8") (pintype "bidirectional"))
      (node (ref "U$20") (pin "1") (pinfunction "S1_1") (pintype "bidirectional"))
      (node (ref "U$20") (pin "2") (pinfunction "S2_2") (pintype "bidirectional"))
      (node (ref "U$20") (pin "3") (pinfunction "S3_3") (pintype "bidirectional"))
      (node (ref "U$26") (pin "13") (pinfunction "13_13") (pintype "bidirectional"))
      (node (ref "U$29") (pin "3") (pinfunction "P$3_3") (pintype "bidirectional"))
    )
    (net (code "56") (name "/SB6") (class "Default")
      (node (ref "U$23") (pin "5") (pinfunction "D4_5") (pintype "bidirectional"))
      (node (ref "U$23") (pin "6") (pinfunction "D3_6") (pintype "bidirectional"))
      (node (ref "U$23") (pin "7") (pinfunction "D2_7") (pintype "bidirectional"))
      (node (ref "U$23") (pin "8") (pinfunction "D1_8") (pintype "bidirectional"))
      (node (ref "U$24") (pin "1") (pinfunction "S1_1") (pintype "bidirectional"))
      (node (ref "U$24") (pin "2") (pinfunction "S2_2") (pintype "bidirectional"))
      (node (ref "U$24") (pin "3") (pinfunction "S3_3") (pintype "bidirectional"))
      (node (ref "U$26") (pin "6") (pinfunction "6_6") (pintype "bidirectional"))
      (node (ref "U$29") (pin "21") (pinfunction "P$21_21") (pintype "bidirectional"))
    )
    (net (code "57") (name "/SCL") (class "Default")
      (node (ref "U$29") (pin "27") (pinfunction "P$27_27") (pintype "bidirectional"))
      (node (ref "U$31") (pin "4") (pinfunction "SCL_4") (pintype "bidirectional"))
    )
    (net (code "58") (name "/SDA") (class "Default")
      (node (ref "U$29") (pin "9") (pinfunction "P$9_9") (pintype "bidirectional"))
      (node (ref "U$31") (pin "6") (pinfunction "SDA_6") (pintype "bidirectional"))
    )
    (net (code "59") (name "/TX") (class "Default")
      (node (ref "U$27") (pin "7") (pinfunction "7_7") (pintype "bidirectional"))
      (node (ref "U$29") (pin "12") (pinfunction "P$12_12") (pintype "bidirectional"))
    )
    (net (code "60") (name "GND") (class "Default")
      (node (ref "R25") (pin "2") (pinfunction "2_2") (pintype "passive"))
      (node (ref "U$1") (pin "1") (pinfunction "S1_1") (pintype "bidirectional"))
      (node (ref "U$1") (pin "2") (pinfunction "S2_2") (pintype "bidirectional"))
      (node (ref "U$1") (pin "3") (pinfunction "S3_3") (pintype "bidirectional"))
      (node (ref "U$11") (pin "1") (pinfunction "S1_1") (pintype "bidirectional"))
      (node (ref "U$11") (pin "2") (pinfunction "S2_2") (pintype "bidirectional"))
      (node (ref "U$11") (pin "3") (pinfunction "S3_3") (pintype "bidirectional"))
      (node (ref "U$13") (pin "1") (pinfunction "S1_1") (pintype "bidirectional"))
      (node (ref "U$13") (pin "2") (pinfunction "S2_2") (pintype "bidirectional"))
      (node (ref "U$13") (pin "3") (pinfunction "S3_3") (pintype "bidirectional"))
      (node (ref "U$15") (pin "1") (pinfunction "S1_1") (pintype "bidirectional"))
      (node (ref "U$15") (pin "2") (pinfunction "S2_2") (pintype "bidirectional"))
      (node (ref "U$15") (pin "3") (pinfunction "S3_3") (pintype "bidirectional"))
      (node (ref "U$17") (pin "1") (pinfunction "S1_1") (pintype "bidirectional"))
      (node (ref "U$17") (pin "2") (pinfunction "S2_2") (pintype "bidirectional"))
      (node (ref "U$17") (pin "3") (pinfunction "S3_3") (pintype "bidirectional"))
      (node (ref "U$19") (pin "1") (pinfunction "S1_1") (pintype "bidirectional"))
      (node (ref "U$19") (pin "2") (pinfunction "S2_2") (pintype "bidirectional"))
      (node (ref "U$19") (pin "3") (pinfunction "S3_3") (pintype "bidirectional"))
      (node (ref "U$21") (pin "1") (pinfunction "S1_1") (pintype "bidirectional"))
      (node (ref "U$21") (pin "2") (pinfunction "S2_2") (pintype "bidirectional"))
      (node (ref "U$21") (pin "3") (pinfunction "S3_3") (pintype "bidirectional"))
      (node (ref "U$23") (pin "1") (pinfunction "S1_1") (pintype "bidirectional"))
      (node (ref "U$23") (pin "2") (pinfunction "S2_2") (pintype "bidirectional"))
      (node (ref "U$23") (pin "3") (pinfunction "S3_3") (pintype "bidirectional"))
      (node (ref "U$25") (pin "10") (pinfunction "10_10") (pintype "bidirectional"))
      (node (ref "U$25") (pin "11") (pinfunction "11_11") (pintype "bidirectional"))
      (node (ref "U$25") (pin "12") (pinfunction "12_12") (pintype "bidirectional"))
      (node (ref "U$25") (pin "5") (pinfunction "5_5") (pintype "bidirectional"))
      (node (ref "U$25") (pin "6") (pinfunction "6_6") (pintype "bidirectional"))
      (node (ref "U$25") (pin "7") (pinfunction "7_7") (pintype "bidirectional"))
      (node (ref "U$25") (pin "8") (pinfunction "8_8") (pintype "bidirectional"))
      (node (ref "U$25") (pin "9") (pinfunction "9_9") (pintype "bidirectional"))
      (node (ref "U$3") (pin "1") (pinfunction "S1_1") (pintype "bidirectional"))
      (node (ref "U$3") (pin "2") (pinfunction "S2_2") (pintype "bidirectional"))
      (node (ref "U$3") (pin "3") (pinfunction "S3_3") (pintype "bidirectional"))
      (node (ref "U$5") (pin "1") (pinfunction "S1_1") (pintype "bidirectional"))
      (node (ref "U$5") (pin "2") (pinfunction "S2_2") (pintype "bidirectional"))
      (node (ref "U$5") (pin "3") (pinfunction "S3_3") (pintype "bidirectional"))
      (node (ref "U$7") (pin "1") (pinfunction "S1_1") (pintype "bidirectional"))
      (node (ref "U$7") (pin "2") (pinfunction "S2_2") (pintype "bidirectional"))
      (node (ref "U$7") (pin "3") (pinfunction "S3_3") (pintype "bidirectional"))
      (node (ref "U$9") (pin "1") (pinfunction "S1_1") (pintype "bidirectional"))
      (node (ref "U$9") (pin "2") (pinfunction "S2_2") (pintype "bidirectional"))
      (node (ref "U$9") (pin "3") (pinfunction "S3_3") (pintype "bidirectional"))
    )
    (net (code "61") (name "Net-(U$1-G)") (class "Default")
      (node (ref "R1") (pin "2") (pinfunction "2_2") (pintype "passive"))
      (node (ref "U$1") (pin "4") (pinfunction "G_4") (pintype "bidirectional"))
    )
    (net (code "62") (name "Net-(U$2-G)") (class "Default")
      (node (ref "R2") (pin "2") (pinfunction "2_2") (pintype "passive"))
      (node (ref "U$2") (pin "4") (pinfunction "G_4") (pintype "bidirectional"))
    )
    (net (code "63") (name "Net-(U$3-G)") (class "Default")
      (node (ref "R3") (pin "1") (pinfunction "1_1") (pintype "passive"))
      (node (ref "U$3") (pin "4") (pinfunction "G_4") (pintype "bidirectional"))
    )
    (net (code "64") (name "Net-(U$4-G)") (class "Default")
      (node (ref "R4") (pin "1") (pinfunction "1_1") (pintype "passive"))
      (node (ref "U$4") (pin "4") (pinfunction "G_4") (pintype "bidirectional"))
    )
    (net (code "65") (name "Net-(U$5-G)") (class "Default")
      (node (ref "R13") (pin "2") (pinfunction "2_2") (pintype "passive"))
      (node (ref "U$5") (pin "4") (pinfunction "G_4") (pintype "bidirectional"))
    )
    (net (code "66") (name "Net-(U$6-G)") (class "Default")
      (node (ref "R14") (pin "2") (pinfunction "2_2") (pintype "passive"))
      (node (ref "U$6") (pin "4") (pinfunction "G_4") (pintype "bidirectional"))
    )
    (net (code "67") (name "Net-(U$7-G)") (class "Default")
      (node (ref "R15") (pin "1") (pinfunction "1_1") (pintype "passive"))
      (node (ref "U$7") (pin "4") (pinfunction "G_4") (pintype "bidirectional"))
    )
    (net (code "68") (name "Net-(U$8-G)") (class "Default")
      (node (ref "R16") (pin "1") (pinfunction "1_1") (pintype "passive"))
      (node (ref "U$8") (pin "4") (pinfunction "G_4") (pintype "bidirectional"))
    )
    (net (code "69") (name "Net-(U$9-G)") (class "Default")
      (node (ref "R5") (pin "2") (pinfunction "2_2") (pintype "passive"))
      (node (ref "U$9") (pin "4") (pinfunction "G_4") (pintype "bidirectional"))
    )
    (net (code "70") (name "Net-(U$10-G)") (class "Default")
      (node (ref "R6") (pin "2") (pinfunction "2_2") (pintype "passive"))
      (node (ref "U$10") (pin "4") (pinfunction "G_4") (pintype "bidirectional"))
    )
    (net (code "71") (name "Net-(U$11-G)") (class "Default")
      (node (ref "R7") (pin "1") (pinfunction "1_1") (pintype "passive"))
      (node (ref "U$11") (pin "4") (pinfunction "G_4") (pintype "bidirectional"))
    )
    (net (code "72") (name "Net-(U$12-G)") (class "Default")
      (node (ref "R8") (pin "1") (pinfunction "1_1") (pintype "passive"))
      (node (ref "U$12") (pin "4") (pinfunction "G_4") (pintype "bidirectional"))
    )
    (net (code "73") (name "Net-(U$13-G)") (class "Default")
      (node (ref "R17") (pin "2") (pinfunction "2_2") (pintype "passive"))
      (node (ref "U$13") (pin "4") (pinfunction "G_4") (pintype "bidirectional"))
    )
    (net (code "74") (name "Net-(U$14-G)") (class "Default")
      (node (ref "R18") (pin "2") (pinfunction "2_2") (pintype "passive"))
      (node (ref "U$14") (pin "4") (pinfunction "G_4") (pintype "bidirectional"))
    )
    (net (code "75") (name "Net-(U$15-G)") (class "Default")
      (node (ref "R19") (pin "1") (pinfunction "1_1") (pintype "passive"))
      (node (ref "U$15") (pin "4") (pinfunction "G_4") (pintype "bidirectional"))
    )
    (net (code "76") (name "Net-(U$16-G)") (class "Default")
      (node (ref "R20") (pin "1") (pinfunction "1_1") (pintype "passive"))
      (node (ref "U$16") (pin "4") (pinfunction "G_4") (pintype "bidirectional"))
    )
    (net (code "77") (name "Net-(U$17-G)") (class "Default")
      (node (ref "R9") (pin "2") (pinfunction "2_2") (pintype "passive"))
      (node (ref "U$17") (pin "4") (pinfunction "G_4") (pintype "bidirectional"))
    )
    (net (code "78") (name "Net-(U$18-G)") (class "Default")
      (node (ref "R10") (pin "2") (pinfunction "2_2") (pintype "passive"))
      (node (ref "U$18") (pin "4") (pinfunction "G_4") (pintype "bidirectional"))
    )
    (net (code "79") (name "Net-(U$19-G)") (class "Default")
      (node (ref "R11") (pin "1") (pinfunction "1_1") (pintype "passive"))
      (node (ref "U$19") (pin "4") (pinfunction "G_4") (pintype "bidirectional"))
    )
    (net (code "80") (name "Net-(U$20-G)") (class "Default")
      (node (ref "R12") (pin "1") (pinfunction "1_1") (pintype "passive"))
      (node (ref "U$20") (pin "4") (pinfunction "G_4") (pintype "bidirectional"))
    )
    (net (code "81") (name "Net-(U$21-G)") (class "Default")
      (node (ref "R21") (pin "2") (pinfunction "2_2") (pintype "passive"))
      (node (ref "U$21") (pin "4") (pinfunction "G_4") (pintype "bidirectional"))
    )
    (net (code "82") (name "Net-(U$22-G)") (class "Default")
      (node (ref "R22") (pin "2") (pinfunction "2_2") (pintype "passive"))
      (node (ref "U$22") (pin "4") (pinfunction "G_4") (pintype "bidirectional"))
    )
    (net (code "83") (name "Net-(U$23-G)") (class "Default")
      (node (ref "R23") (pin "1") (pinfunction "1_1") (pintype "passive"))
      (node (ref "U$23") (pin "4") (pinfunction "G_4") (pintype "bidirectional"))
    )
    (net (code "84") (name "Net-(U$24-G)") (class "Default")
      (node (ref "R24") (pin "1") (pinfunction "1_1") (pintype "passive"))
      (node (ref "U$24") (pin "4") (pinfunction "G_4") (pintype "bidirectional"))
    )
    (net (code "85") (name "unconnected-(U$31-ALRT-Pad5)") (class "Default")
      (node (ref "U$31") (pin "5") (pinfunction "ALRT_5") (pintype "bidirectional"))
    )
    (net (code "86") (name "unconnected-(U$31-AS-Pad1)") (class "Default")
      (node (ref "U$31") (pin "1") (pinfunction "AS_1") (pintype "bidirectional"))
    )
  )
)
